# badito_V5.net
KiCad netlist of a schematic drawn in EAGLE
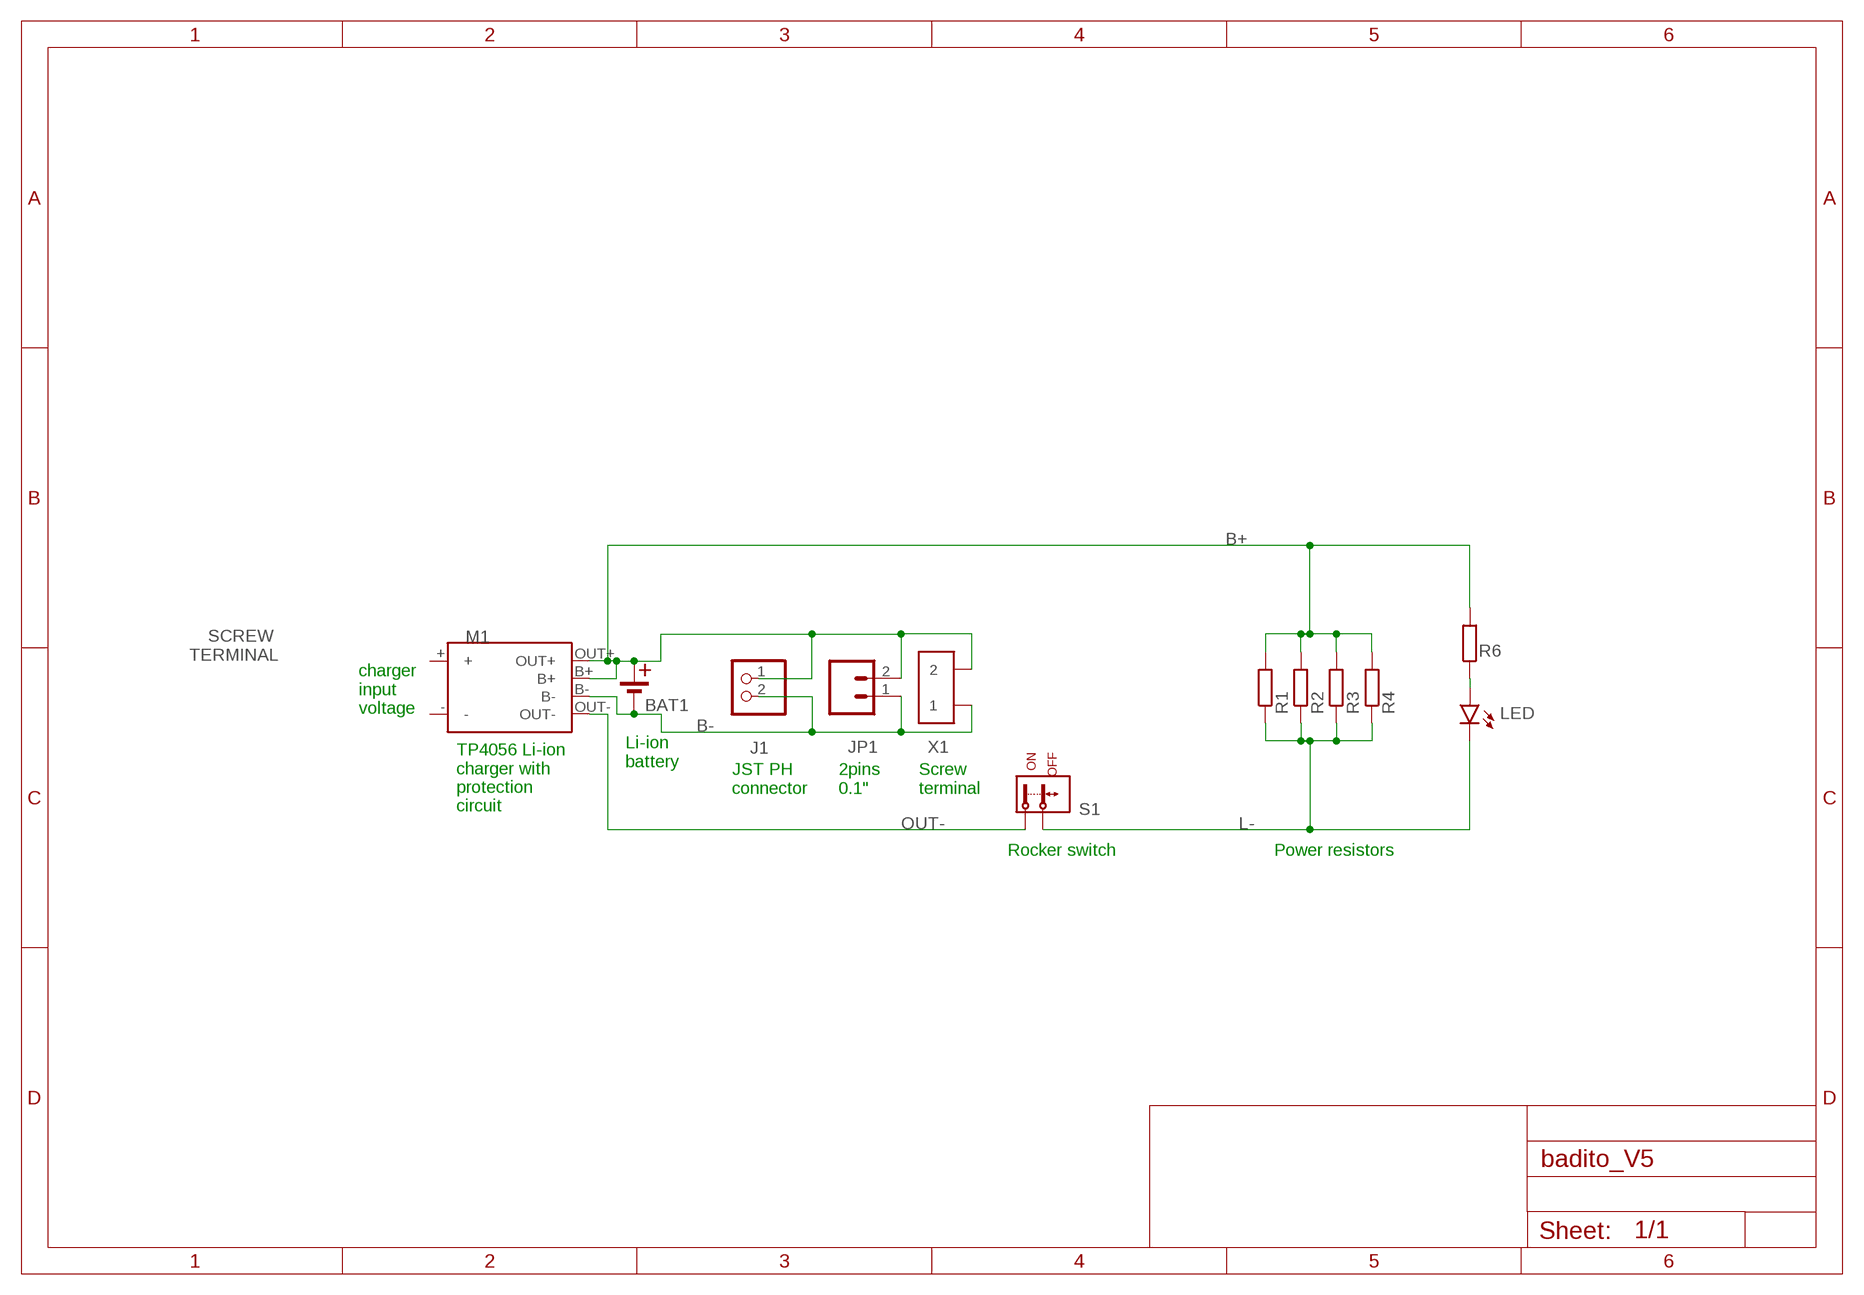
[diagram p0: schematic, sheet 1]

(export (version "E")
  (design (tool "Eeschema 10.0.6"))
  (components
    (comp (ref "BAT1")
      (value "KS18650X1-SMT")
      (footprint "eagle-import:KS18650X1-SMT")
      (libsource (lib "eagle-import") (part "KS18650X1-SMT"))
    )
    (comp (ref "J1")
      (value "JST_2PIN-SMT")
      (footprint "eagle-import:JST-PH-2-SMT")
      (libsource (lib "eagle-import") (part "JST_2PIN-SMT"))
    )
    (comp (ref "JP1")
      (value "1X02_2.54MM_ROUND")
      (footprint "eagle-import:1X02_2.54MM_ROUND")
      (fields (field (name "MPN") "2211S-02G "))
      (libsource (lib "eagle-import") (part "1X02_2.54MM_ROUND"))
    )
    (comp (ref "LED")
      (value "RED")
      (footprint "eagle-import:LED-0603")
      (fields (field (name "MF") "Kingbright") (field (name "MPN") "KPT-1608SURCK"))
      (libsource (lib "eagle-import") (part "LED0603-RED"))
    )
    (comp (ref "M1")
      (value "TP4056_CHG_PROT")
      (footprint "eagle-import:BAT_CHG_PROT_BRD_27.9X17.4MM")
      (libsource (lib "eagle-import") (part "TP4056_CHG_PROT"))
    )
    (comp (ref "R1")
      (value "R")
      (footprint "eagle-import:R_PWR_CEMENT_10W")
      (libsource (lib "eagle-import") (part "R"))
    )
    (comp (ref "R2")
      (value "R")
      (footprint "eagle-import:R_PWR_CEMENT_10W")
      (libsource (lib "eagle-import") (part "R"))
    )
    (comp (ref "R3")
      (value "R")
      (footprint "eagle-import:R_PWR_CEMENT_10W")
      (libsource (lib "eagle-import") (part "R"))
    )
    (comp (ref "R4")
      (value "R")
      (footprint "eagle-import:R_PWR_CEMENT_10W")
      (libsource (lib "eagle-import") (part "R"))
    )
    (comp (ref "R6")
      (value "250R")
      (footprint "eagle-import:R0603")
      (libsource (lib "eagle-import") (part "R0603_300R"))
    )
    (comp (ref "S1")
      (value "SWITCH_ROCKER_KCDI-101")
      (footprint "eagle-import:SWITCH_ROCKER_KCDI-101")
      (libsource (lib "eagle-import") (part "SWITCH_ROCKER_KCDI-101"))
    )
    (comp (ref "X1")
      (value "ED350/2")
      (footprint "eagle-import:ED350_2")
      (libsource (lib "eagle-import") (part "ED350/2"))
    )
  )
  (nets
    (net (code "1") (name "/B+") (class "Default")
      (node (ref "BAT1") (pin "+") (pinfunction "+_+") (pintype "passive"))
      (node (ref "J1") (pin "1") (pinfunction "2_1") (pintype "passive"))
      (node (ref "JP1") (pin "2") (pinfunction "2_2") (pintype "passive"))
      (node (ref "M1") (pin "B+") (pinfunction "B+_B+") (pintype "bidirectional"))
      (node (ref "M1") (pin "OUT+") (pinfunction "OUT+_OUT+") (pintype "bidirectional"))
      (node (ref "R1") (pin "1") (pinfunction "2_1") (pintype "passive"))
      (node (ref "R2") (pin "1") (pinfunction "2_1") (pintype "passive"))
      (node (ref "R3") (pin "1") (pinfunction "2_1") (pintype "passive"))
      (node (ref "R4") (pin "1") (pinfunction "2_1") (pintype "passive"))
      (node (ref "R6") (pin "2") (pinfunction "2_2") (pintype "passive"))
      (node (ref "X1") (pin "P$2") (pinfunction "2_P$2") (pintype "bidirectional"))
    )
    (net (code "2") (name "/B-") (class "Default")
      (node (ref "BAT1") (pin "-") (pinfunction "-_-") (pintype "passive"))
      (node (ref "J1") (pin "2") (pinfunction "1_2") (pintype "passive"))
      (node (ref "JP1") (pin "1") (pinfunction "1_1") (pintype "passive"))
      (node (ref "M1") (pin "B-") (pinfunction "B-_B-") (pintype "bidirectional"))
      (node (ref "X1") (pin "P$1") (pinfunction "1_P$1") (pintype "bidirectional"))
    )
    (net (code "3") (name "/L-") (class "Default")
      (node (ref "LED") (pin "C") (pinfunction "C_C") (pintype "passive"))
      (node (ref "R1") (pin "2") (pinfunction "1_2") (pintype "passive"))
      (node (ref "R2") (pin "2") (pinfunction "1_2") (pintype "passive"))
      (node (ref "R3") (pin "2") (pinfunction "1_2") (pintype "passive"))
      (node (ref "R4") (pin "2") (pinfunction "1_2") (pintype "passive"))
      (node (ref "S1") (pin "2") (pinfunction "2.1_2") (pintype "passive"))
      (node (ref "S1") (pin "2_2") (pinfunction "2.1_2_2") (pintype "passive"))
    )
    (net (code "4") (name "/OUT-") (class "Default")
      (node (ref "M1") (pin "OUT-") (pinfunction "OUT-_OUT-") (pintype "bidirectional"))
      (node (ref "S1") (pin "1") (pinfunction "1.1_1") (pintype "passive"))
      (node (ref "S1") (pin "1_1") (pinfunction "1.1_1_1") (pintype "passive"))
    )
    (net (code "5") (name "Net-(LED-PadA)") (class "Default")
      (node (ref "LED") (pin "A") (pinfunction "A_A") (pintype "passive"))
      (node (ref "R6") (pin "1") (pinfunction "1_1") (pintype "passive"))
    )
    (net (code "6") (name "unconnected-(M1-Pad+)") (class "Default")
      (node (ref "M1") (pin "+") (pinfunction "+_+") (pintype "bidirectional"))
    )
    (net (code "7") (name "unconnected-(M1-Pad-)") (class "Default")
      (node (ref "M1") (pin "-") (pinfunction "-_-") (pintype "bidirectional"))
    )
  )
)
